# ESP_Adapter_Board_GPIO_PIN.net
KiCad netlist of a schematic drawn in Altium Designer
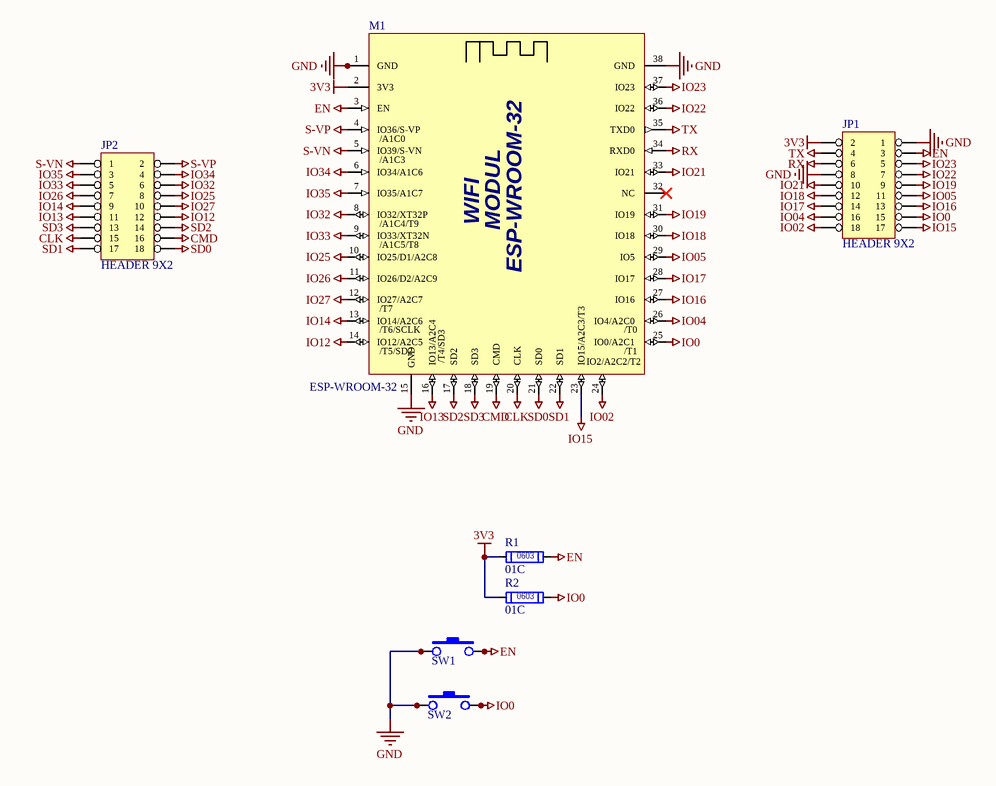
[diagram p0: ESP_Adapter_Board_GPIO_PIN.SchDoc]

(export (version "E")
  (design (tool "Eeschema 10.0.6"))
  (components
    (comp (ref "JP1") (value "HEADER 9X2") (footprint "H 9x2") (libsource (lib "") (part "HEADER 9X2_1")))
    (comp (ref "JP2")
      (value "HEADER 9X2")
      (footprint "H 9x2")
      (libsource (lib "CONNECTOR") (part "HEADER 9X2"))
    )
    (comp (ref "M1")
      (value "ESP-WROOM-32")
      (footprint "WIFI MODUL ESP-WROOM-32")
      (libsource (lib "MODUL") (part "WIFI MODUL ESP-WROOM-32"))
    )
    (comp (ref "R1")
      (value "01C")
      (footprint "CRES1608-0603 3D")
      (description "RES_SMD0603 0.100W")
      (libsource (lib "RESISTOR") (part "RES_SMD0603 0.100W"))
    )
    (comp (ref "R2")
      (value "01C")
      (footprint "CRES1608-0603 3D")
      (description "RES_SMD0603 0.100W")
      (libsource (lib "RESISTOR") (part "RES_SMD0603 0.100W"))
    )
    (comp (ref "SW1")
      (value "REG")
      (footprint "SMD TAC SW 6x6x4.3mm")
      (description "4 PIN")
      (libsource (lib "SWITCH") (part "SW PB - TAC2"))
    )
    (comp (ref "SW2")
      (value "REG")
      (footprint "SMD TAC SW 6x6x4.3mm")
      (description "4 PIN")
      (libsource (lib "SWITCH") (part "SW PB - TAC2"))
    )
  )
  (nets
    (net (code "1") (name "3V3") (class "Default")
      (node (ref "JP1") (pin "2") (pinfunction "2_2") (pintype "passive"))
      (node (ref "M1") (pin "2") (pinfunction "3V3_2") (pintype "power_in"))
      (node (ref "R1") (pin "1") (pinfunction "1_1") (pintype "passive"))
      (node (ref "R2") (pin "1") (pinfunction "1_1") (pintype "passive"))
    )
    (net (code "2") (name "CLK") (class "Default")
      (node (ref "JP2") (pin "15") (pinfunction "15_15") (pintype "passive"))
      (node (ref "M1") (pin "20") (pinfunction "CLK_20") (pintype "bidirectional"))
    )
    (net (code "3") (name "CMD") (class "Default")
      (node (ref "JP2") (pin "16") (pinfunction "16_16") (pintype "passive"))
      (node (ref "M1") (pin "19") (pinfunction "CMD_19") (pintype "bidirectional"))
    )
    (net (code "4") (name "EN") (class "Default")
      (node (ref "JP1") (pin "3") (pinfunction "3_3") (pintype "passive"))
      (node (ref "M1") (pin "3") (pinfunction "EN_3") (pintype "input"))
      (node (ref "R1") (pin "2") (pinfunction "2_2") (pintype "passive"))
      (node (ref "SW1") (pin "3") (pinfunction "3_3") (pintype "passive"))
      (node (ref "SW1") (pin "4") (pinfunction "4_4") (pintype "passive"))
    )
    (net (code "5") (name "GND") (class "Default")
      (node (ref "JP1") (pin "1") (pinfunction "1_1") (pintype "passive"))
      (node (ref "JP1") (pin "8") (pinfunction "8_8") (pintype "passive"))
      (node (ref "M1") (pin "0") (pinfunction "GND_0") (pintype "power_in"))
      (node (ref "M1") (pin "1") (pinfunction "GND_1") (pintype "power_in"))
      (node (ref "M1") (pin "15") (pinfunction "GND_15") (pintype "power_in"))
      (node (ref "M1") (pin "38") (pinfunction "GND_38") (pintype "power_in"))
      (node (ref "SW1") (pin "1") (pinfunction "1_1") (pintype "passive"))
      (node (ref "SW1") (pin "2") (pinfunction "2_2") (pintype "passive"))
      (node (ref "SW2") (pin "1") (pinfunction "1_1") (pintype "passive"))
      (node (ref "SW2") (pin "2") (pinfunction "2_2") (pintype "passive"))
    )
    (net (code "6") (name "IO0") (class "Default")
      (node (ref "JP1") (pin "15") (pinfunction "15_15") (pintype "passive"))
      (node (ref "M1") (pin "25") (pinfunction "IO0/A2C1_25") (pintype "bidirectional"))
      (node (ref "R2") (pin "2") (pinfunction "2_2") (pintype "passive"))
      (node (ref "SW2") (pin "3") (pinfunction "3_3") (pintype "passive"))
      (node (ref "SW2") (pin "4") (pinfunction "4_4") (pintype "passive"))
    )
    (net (code "7") (name "IO02") (class "Default")
      (node (ref "JP1") (pin "18") (pinfunction "18_18") (pintype "passive"))
      (node (ref "M1") (pin "24") (pinfunction "IO2/A2C2/T2_24") (pintype "bidirectional"))
    )
    (net (code "8") (name "IO04") (class "Default")
      (node (ref "JP1") (pin "16") (pinfunction "16_16") (pintype "passive"))
      (node (ref "M1") (pin "26") (pinfunction "IO4/A2C0_26") (pintype "bidirectional"))
    )
    (net (code "9") (name "IO05") (class "Default")
      (node (ref "JP1") (pin "11") (pinfunction "11_11") (pintype "passive"))
      (node (ref "M1") (pin "29") (pinfunction "IO5_29") (pintype "bidirectional"))
    )
    (net (code "10") (name "IO12") (class "Default")
      (node (ref "JP2") (pin "12") (pinfunction "12_12") (pintype "passive"))
      (node (ref "M1") (pin "14") (pinfunction "IO12/A2C5_14") (pintype "bidirectional"))
    )
    (net (code "11") (name "IO13") (class "Default")
      (node (ref "JP2") (pin "11") (pinfunction "11_11") (pintype "passive"))
      (node (ref "M1") (pin "16") (pinfunction "IO13/A2C4_16") (pintype "bidirectional"))
    )
    (net (code "12") (name "IO14") (class "Default")
      (node (ref "JP2") (pin "9") (pinfunction "9_9") (pintype "passive"))
      (node (ref "M1") (pin "13") (pinfunction "IO14/A2C6_13") (pintype "bidirectional"))
    )
    (net (code "13") (name "IO15") (class "Default")
      (node (ref "JP1") (pin "17") (pinfunction "17_17") (pintype "passive"))
      (node (ref "M1") (pin "23") (pinfunction "IO15/A2C3/T3_23") (pintype "bidirectional"))
    )
    (net (code "14") (name "IO16") (class "Default")
      (node (ref "JP1") (pin "13") (pinfunction "13_13") (pintype "passive"))
      (node (ref "M1") (pin "27") (pinfunction "IO16_27") (pintype "bidirectional"))
    )
    (net (code "15") (name "IO17") (class "Default")
      (node (ref "JP1") (pin "14") (pinfunction "14_14") (pintype "passive"))
      (node (ref "M1") (pin "28") (pinfunction "IO17_28") (pintype "bidirectional"))
    )
    (net (code "16") (name "IO18") (class "Default")
      (node (ref "JP1") (pin "12") (pinfunction "12_12") (pintype "passive"))
      (node (ref "M1") (pin "30") (pinfunction "IO18_30") (pintype "bidirectional"))
    )
    (net (code "17") (name "IO19") (class "Default")
      (node (ref "JP1") (pin "9") (pinfunction "9_9") (pintype "passive"))
      (node (ref "M1") (pin "31") (pinfunction "IO19_31") (pintype "bidirectional"))
    )
    (net (code "18") (name "IO21") (class "Default")
      (node (ref "JP1") (pin "10") (pinfunction "10_10") (pintype "passive"))
      (node (ref "M1") (pin "33") (pinfunction "IO21_33") (pintype "bidirectional"))
    )
    (net (code "19") (name "IO22") (class "Default")
      (node (ref "JP1") (pin "7") (pinfunction "7_7") (pintype "passive"))
      (node (ref "M1") (pin "36") (pinfunction "IO22_36") (pintype "bidirectional"))
    )
    (net (code "20") (name "IO23") (class "Default")
      (node (ref "JP1") (pin "5") (pinfunction "5_5") (pintype "passive"))
      (node (ref "M1") (pin "37") (pinfunction "IO23_37") (pintype "bidirectional"))
    )
    (net (code "21") (name "IO25") (class "Default")
      (node (ref "JP2") (pin "8") (pinfunction "8_8") (pintype "passive"))
      (node (ref "M1") (pin "10") (pinfunction "IO25/D1/A2C8_10") (pintype "bidirectional"))
    )
    (net (code "22") (name "IO26") (class "Default")
      (node (ref "JP2") (pin "7") (pinfunction "7_7") (pintype "passive"))
      (node (ref "M1") (pin "11") (pinfunction "IO26/D2/A2C9_11") (pintype "bidirectional"))
    )
    (net (code "23") (name "IO27") (class "Default")
      (node (ref "JP2") (pin "10") (pinfunction "10_10") (pintype "passive"))
      (node (ref "M1") (pin "12") (pinfunction "IO27/A2C7_12") (pintype "bidirectional"))
    )
    (net (code "24") (name "IO32") (class "Default")
      (node (ref "JP2") (pin "6") (pinfunction "6_6") (pintype "passive"))
      (node (ref "M1") (pin "8") (pinfunction "IO32/XT32P_8") (pintype "bidirectional"))
    )
    (net (code "25") (name "IO33") (class "Default")
      (node (ref "JP2") (pin "5") (pinfunction "5_5") (pintype "passive"))
      (node (ref "M1") (pin "9") (pinfunction "IO33/XT32N_9") (pintype "bidirectional"))
    )
    (net (code "26") (name "IO34") (class "Default")
      (node (ref "JP2") (pin "4") (pinfunction "4_4") (pintype "passive"))
      (node (ref "M1") (pin "6") (pinfunction "IO34/A1C6_6") (pintype "input"))
    )
    (net (code "27") (name "IO35") (class "Default")
      (node (ref "JP2") (pin "3") (pinfunction "3_3") (pintype "passive"))
      (node (ref "M1") (pin "7") (pinfunction "IO35/A1C7_7") (pintype "input"))
    )
    (net (code "28") (name "RX") (class "Default")
      (node (ref "JP1") (pin "6") (pinfunction "6_6") (pintype "passive"))
      (node (ref "M1") (pin "34") (pinfunction "RXD0_34") (pintype "input"))
    )
    (net (code "29") (name "S-VN") (class "Default")
      (node (ref "JP2") (pin "1") (pinfunction "1_1") (pintype "passive"))
      (node (ref "M1") (pin "5") (pinfunction "IO39/S-VN_5") (pintype "input"))
    )
    (net (code "30") (name "S-VP") (class "Default")
      (node (ref "JP2") (pin "2") (pinfunction "2_2") (pintype "passive"))
      (node (ref "M1") (pin "4") (pinfunction "IO36/S-VP_4") (pintype "input"))
    )
    (net (code "31") (name "SD0") (class "Default")
      (node (ref "JP2") (pin "18") (pinfunction "18_18") (pintype "passive"))
      (node (ref "M1") (pin "21") (pinfunction "SD0_21") (pintype "bidirectional"))
    )
    (net (code "32") (name "SD1") (class "Default")
      (node (ref "JP2") (pin "17") (pinfunction "17_17") (pintype "passive"))
      (node (ref "M1") (pin "22") (pinfunction "SD1_22") (pintype "bidirectional"))
    )
    (net (code "33") (name "SD2") (class "Default")
      (node (ref "JP2") (pin "14") (pinfunction "14_14") (pintype "passive"))
      (node (ref "M1") (pin "17") (pinfunction "SD2_17") (pintype "bidirectional"))
    )
    (net (code "34") (name "SD3") (class "Default")
      (node (ref "JP2") (pin "13") (pinfunction "13_13") (pintype "passive"))
      (node (ref "M1") (pin "18") (pinfunction "SD3_18") (pintype "bidirectional"))
    )
    (net (code "35") (name "TX") (class "Default")
      (node (ref "JP1") (pin "4") (pinfunction "4_4") (pintype "passive"))
      (node (ref "M1") (pin "35") (pinfunction "TXD0_35") (pintype "output"))
    )
    (net (code "36") (name "unconnected-(M1-NC-Pad32)") (class "Default")
      (node (ref "M1") (pin "32") (pinfunction "NC_32") (pintype "passive+no_connect"))
    )
  )
)
